# ir_ring_2022_neu_03.net
KiCad netlist of a schematic drawn in EAGLE
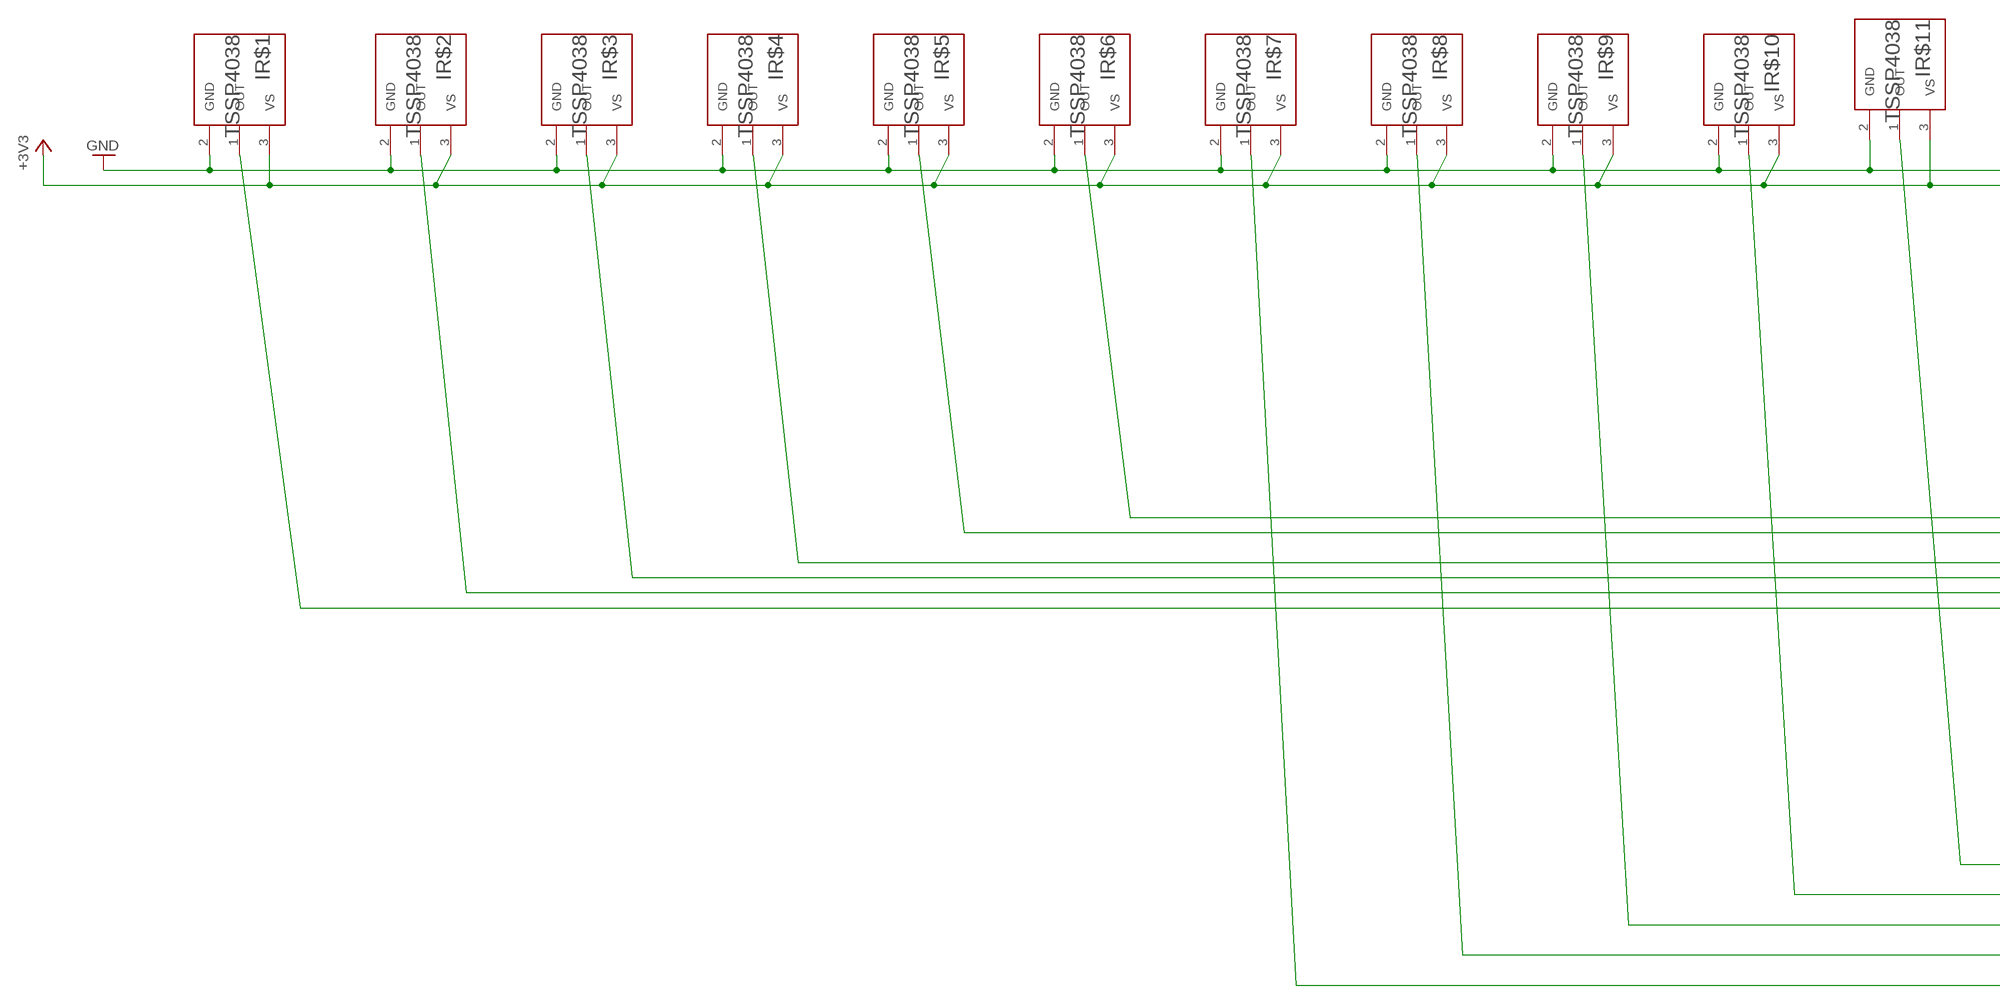
[diagram p0: schematic, sheet 1, part 1 of 2]
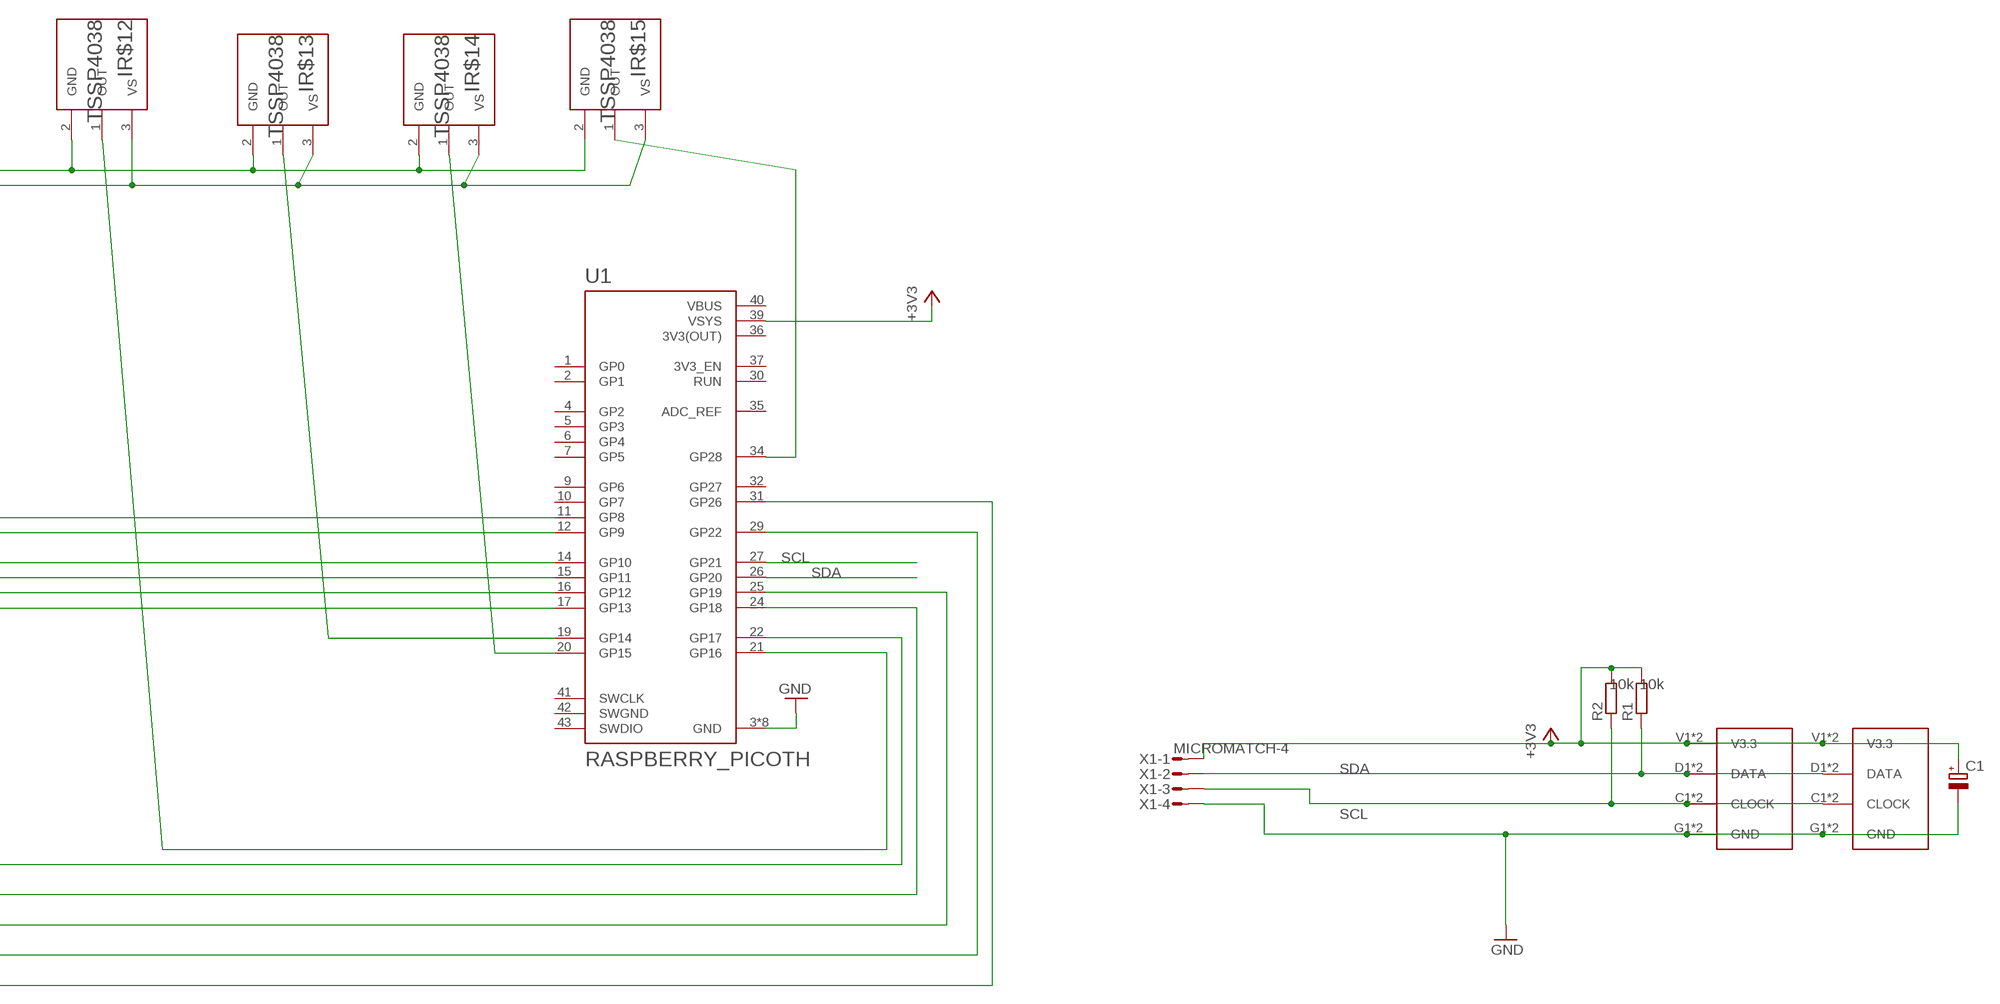
[diagram p1: schematic, sheet 1, part 2 of 2]

(export (version "E")
  (design (tool "Eeschema 10.0.6"))
  (components
    (comp (ref "C1")
      (value "CPOL-EUE2-5")
      (footprint "eagle-import:E2-5")
      (libsource (lib "eagle-import") (part "CPOL-EUE2-5"))
    )
    (comp (ref "IR$1")
      (value "TSSP4038")
      (footprint "eagle-import:XDCR_TSSP4038")
      (fields (field (name "MF") "Vishay Semiconductor"))
      (libsource (lib "eagle-import") (part "TSSP4038"))
    )
    (comp (ref "IR$2")
      (value "TSSP4038")
      (footprint "eagle-import:XDCR_TSSP4038")
      (fields (field (name "MF") "Vishay Semiconductor"))
      (libsource (lib "eagle-import") (part "TSSP4038"))
    )
    (comp (ref "IR$3")
      (value "TSSP4038")
      (footprint "eagle-import:XDCR_TSSP4038")
      (fields (field (name "MF") "Vishay Semiconductor"))
      (libsource (lib "eagle-import") (part "TSSP4038"))
    )
    (comp (ref "IR$4")
      (value "TSSP4038")
      (footprint "eagle-import:XDCR_TSSP4038")
      (fields (field (name "MF") "Vishay Semiconductor"))
      (libsource (lib "eagle-import") (part "TSSP4038"))
    )
    (comp (ref "IR$5")
      (value "TSSP4038")
      (footprint "eagle-import:XDCR_TSSP4038")
      (fields (field (name "MF") "Vishay Semiconductor"))
      (libsource (lib "eagle-import") (part "TSSP4038"))
    )
    (comp (ref "IR$6")
      (value "TSSP4038")
      (footprint "eagle-import:XDCR_TSSP4038")
      (fields (field (name "MF") "Vishay Semiconductor"))
      (libsource (lib "eagle-import") (part "TSSP4038"))
    )
    (comp (ref "IR$7")
      (value "TSSP4038")
      (footprint "eagle-import:XDCR_TSSP4038")
      (fields (field (name "MF") "Vishay Semiconductor"))
      (libsource (lib "eagle-import") (part "TSSP4038"))
    )
    (comp (ref "IR$8")
      (value "TSSP4038")
      (footprint "eagle-import:XDCR_TSSP4038")
      (fields (field (name "MF") "Vishay Semiconductor"))
      (libsource (lib "eagle-import") (part "TSSP4038"))
    )
    (comp (ref "IR$9")
      (value "TSSP4038")
      (footprint "eagle-import:XDCR_TSSP4038")
      (fields (field (name "MF") "Vishay Semiconductor"))
      (libsource (lib "eagle-import") (part "TSSP4038"))
    )
    (comp (ref "IR$10")
      (value "TSSP4038")
      (footprint "eagle-import:XDCR_TSSP4038")
      (fields (field (name "MF") "Vishay Semiconductor"))
      (libsource (lib "eagle-import") (part "TSSP4038"))
    )
    (comp (ref "IR$11")
      (value "TSSP4038")
      (footprint "eagle-import:XDCR_TSSP4038")
      (fields (field (name "MF") "Vishay Semiconductor"))
      (libsource (lib "eagle-import") (part "TSSP4038"))
    )
    (comp (ref "IR$12")
      (value "TSSP4038")
      (footprint "eagle-import:XDCR_TSSP4038")
      (fields (field (name "MF") "Vishay Semiconductor"))
      (libsource (lib "eagle-import") (part "TSSP4038"))
    )
    (comp (ref "IR$13")
      (value "TSSP4038")
      (footprint "eagle-import:XDCR_TSSP4038")
      (fields (field (name "MF") "Vishay Semiconductor"))
      (libsource (lib "eagle-import") (part "TSSP4038"))
    )
    (comp (ref "IR$14")
      (value "TSSP4038")
      (footprint "eagle-import:XDCR_TSSP4038")
      (fields (field (name "MF") "Vishay Semiconductor"))
      (libsource (lib "eagle-import") (part "TSSP4038"))
    )
    (comp (ref "IR$15")
      (value "TSSP4038")
      (footprint "eagle-import:XDCR_TSSP4038")
      (fields (field (name "MF") "Vishay Semiconductor"))
      (libsource (lib "eagle-import") (part "TSSP4038"))
    )
    (comp (ref "R1")
      (value "10k")
      (footprint "eagle-import:0204_7")
      (libsource (lib "eagle-import") (part "R-EU_0204/7"))
    )
    (comp (ref "R2")
      (value "10k")
      (footprint "eagle-import:0204_7")
      (libsource (lib "eagle-import") (part "R-EU_0204/7"))
    )
    (comp (ref "U$1")
      (value "TASTER_LED")
      (footprint "eagle-import:TASTER_LED")
      (libsource (lib "eagle-import") (part "TASTER_LED"))
    )
    (comp (ref "U$2")
      (value "TASTER_LED")
      (footprint "eagle-import:TASTER_LED")
      (libsource (lib "eagle-import") (part "TASTER_LED"))
    )
    (comp (ref "U1")
      (value "RASPBERRY_PICOTH")
      (footprint "eagle-import:PICO-PKG-TH")
      (libsource (lib "eagle-import") (part "RASPBERRY_PICOTH"))
    )
    (comp (ref "X1")
      (value "MICROMATCH-4")
      (footprint "eagle-import:MICROMATCH-4")
      (fields (field (name "MPN") "7-215464-4"))
      (libsource (lib "eagle-import") (part "MICROMATCH-4"))
    )
  )
  (nets
    (net (code "1") (name "+3V3") (class "Default")
      (node (ref "C1") (pin "+") (pinfunction "+_+") (pintype "passive"))
      (node (ref "IR$1") (pin "3") (pinfunction "VS_3") (pintype "power_in"))
      (node (ref "IR$10") (pin "3") (pinfunction "VS_3") (pintype "power_in"))
      (node (ref "IR$11") (pin "3") (pinfunction "VS_3") (pintype "power_in"))
      (node (ref "IR$12") (pin "3") (pinfunction "VS_3") (pintype "power_in"))
      (node (ref "IR$13") (pin "3") (pinfunction "VS_3") (pintype "power_in"))
      (node (ref "IR$14") (pin "3") (pinfunction "VS_3") (pintype "power_in"))
      (node (ref "IR$15") (pin "3") (pinfunction "VS_3") (pintype "power_in"))
      (node (ref "IR$2") (pin "3") (pinfunction "VS_3") (pintype "power_in"))
      (node (ref "IR$3") (pin "3") (pinfunction "VS_3") (pintype "power_in"))
      (node (ref "IR$4") (pin "3") (pinfunction "VS_3") (pintype "power_in"))
      (node (ref "IR$5") (pin "3") (pinfunction "VS_3") (pintype "power_in"))
      (node (ref "IR$6") (pin "3") (pinfunction "VS_3") (pintype "power_in"))
      (node (ref "IR$7") (pin "3") (pinfunction "VS_3") (pintype "power_in"))
      (node (ref "IR$8") (pin "3") (pinfunction "VS_3") (pintype "power_in"))
      (node (ref "IR$9") (pin "3") (pinfunction "VS_3") (pintype "power_in"))
      (node (ref "R1") (pin "2") (pinfunction "2_2") (pintype "passive"))
      (node (ref "R2") (pin "2") (pinfunction "2_2") (pintype "passive"))
      (node (ref "U$1") (pin "V1") (pinfunction "V3.3_V1") (pintype "bidirectional"))
      (node (ref "U$1") (pin "V2") (pinfunction "V3.3_V2") (pintype "bidirectional"))
      (node (ref "U$2") (pin "V1") (pinfunction "V3.3_V1") (pintype "bidirectional"))
      (node (ref "U$2") (pin "V2") (pinfunction "V3.3_V2") (pintype "bidirectional"))
      (node (ref "U1") (pin "39") (pinfunction "VSYS_39") (pintype "power_in"))
      (node (ref "X1") (pin "1") (pinfunction "S_1") (pintype "passive"))
    )
    (net (code "2") (name "/3V3(OUT)") (class "Default")
      (node (ref "U1") (pin "36") (pinfunction "3V3(OUT)_36") (pintype "power_in"))
    )
    (net (code "3") (name "/SCL") (class "Default")
      (node (ref "R2") (pin "1") (pinfunction "1_1") (pintype "passive"))
      (node (ref "U$1") (pin "C1") (pinfunction "CLOCK_C1") (pintype "bidirectional"))
      (node (ref "U$1") (pin "C2") (pinfunction "CLOCK_C2") (pintype "bidirectional"))
      (node (ref "U$2") (pin "C1") (pinfunction "CLOCK_C1") (pintype "bidirectional"))
      (node (ref "U$2") (pin "C2") (pinfunction "CLOCK_C2") (pintype "bidirectional"))
      (node (ref "U1") (pin "27") (pinfunction "GP21_27") (pintype "bidirectional"))
      (node (ref "X1") (pin "3") (pinfunction "S_3") (pintype "passive"))
    )
    (net (code "4") (name "/SDA") (class "Default")
      (node (ref "R1") (pin "1") (pinfunction "1_1") (pintype "passive"))
      (node (ref "U$1") (pin "D1") (pinfunction "DATA_D1") (pintype "bidirectional"))
      (node (ref "U$1") (pin "D2") (pinfunction "DATA_D2") (pintype "bidirectional"))
      (node (ref "U$2") (pin "D1") (pinfunction "DATA_D1") (pintype "bidirectional"))
      (node (ref "U$2") (pin "D2") (pinfunction "DATA_D2") (pintype "bidirectional"))
      (node (ref "U1") (pin "26") (pinfunction "GP20_26") (pintype "bidirectional"))
      (node (ref "X1") (pin "2") (pinfunction "S_2") (pintype "passive"))
    )
    (net (code "5") (name "/SWGND") (class "Default")
      (node (ref "U1") (pin "42") (pinfunction "SWGND_42") (pintype "power_in"))
    )
    (net (code "6") (name "/VBUS") (class "Default")
      (node (ref "U1") (pin "40") (pinfunction "VBUS_40") (pintype "power_in"))
    )
    (net (code "7") (name "GND") (class "Default")
      (node (ref "C1") (pin "-") (pinfunction "-_-") (pintype "passive"))
      (node (ref "IR$1") (pin "2") (pinfunction "GND_2") (pintype "power_in"))
      (node (ref "IR$10") (pin "2") (pinfunction "GND_2") (pintype "power_in"))
      (node (ref "IR$11") (pin "2") (pinfunction "GND_2") (pintype "power_in"))
      (node (ref "IR$12") (pin "2") (pinfunction "GND_2") (pintype "power_in"))
      (node (ref "IR$13") (pin "2") (pinfunction "GND_2") (pintype "power_in"))
      (node (ref "IR$14") (pin "2") (pinfunction "GND_2") (pintype "power_in"))
      (node (ref "IR$15") (pin "2") (pinfunction "GND_2") (pintype "power_in"))
      (node (ref "IR$2") (pin "2") (pinfunction "GND_2") (pintype "power_in"))
      (node (ref "IR$3") (pin "2") (pinfunction "GND_2") (pintype "power_in"))
      (node (ref "IR$4") (pin "2") (pinfunction "GND_2") (pintype "power_in"))
      (node (ref "IR$5") (pin "2") (pinfunction "GND_2") (pintype "power_in"))
      (node (ref "IR$6") (pin "2") (pinfunction "GND_2") (pintype "power_in"))
      (node (ref "IR$7") (pin "2") (pinfunction "GND_2") (pintype "power_in"))
      (node (ref "IR$8") (pin "2") (pinfunction "GND_2") (pintype "power_in"))
      (node (ref "IR$9") (pin "2") (pinfunction "GND_2") (pintype "power_in"))
      (node (ref "U$1") (pin "G1") (pinfunction "GND_G1") (pintype "bidirectional"))
      (node (ref "U$1") (pin "G2") (pinfunction "GND_G2") (pintype "bidirectional"))
      (node (ref "U$2") (pin "G1") (pinfunction "GND_G1") (pintype "bidirectional"))
      (node (ref "U$2") (pin "G2") (pinfunction "GND_G2") (pintype "bidirectional"))
      (node (ref "U1") (pin "13") (pinfunction "GND_13") (pintype "power_in"))
      (node (ref "U1") (pin "18") (pinfunction "GND_18") (pintype "power_in"))
      (node (ref "U1") (pin "23") (pinfunction "GND_23") (pintype "power_in"))
      (node (ref "U1") (pin "28") (pinfunction "GND_28") (pintype "power_in"))
      (node (ref "U1") (pin "3") (pinfunction "GND_3") (pintype "power_in"))
      (node (ref "U1") (pin "33") (pinfunction "GND_33") (pintype "power_in"))
      (node (ref "U1") (pin "38") (pinfunction "GND_38") (pintype "power_in"))
      (node (ref "U1") (pin "8") (pinfunction "GND_8") (pintype "power_in"))
      (node (ref "X1") (pin "4") (pinfunction "S_4") (pintype "passive"))
    )
    (net (code "8") (name "Net-(IR$1-OUT)") (class "Default")
      (node (ref "IR$1") (pin "1") (pinfunction "OUT_1") (pintype "output"))
      (node (ref "U1") (pin "17") (pinfunction "GP13_17") (pintype "bidirectional"))
    )
    (net (code "9") (name "Net-(IR$2-OUT)") (class "Default")
      (node (ref "IR$2") (pin "1") (pinfunction "OUT_1") (pintype "output"))
      (node (ref "U1") (pin "16") (pinfunction "GP12_16") (pintype "bidirectional"))
    )
    (net (code "10") (name "Net-(IR$3-OUT)") (class "Default")
      (node (ref "IR$3") (pin "1") (pinfunction "OUT_1") (pintype "output"))
      (node (ref "U1") (pin "15") (pinfunction "GP11_15") (pintype "bidirectional"))
    )
    (net (code "11") (name "Net-(IR$4-OUT)") (class "Default")
      (node (ref "IR$4") (pin "1") (pinfunction "OUT_1") (pintype "output"))
      (node (ref "U1") (pin "14") (pinfunction "GP10_14") (pintype "bidirectional"))
    )
    (net (code "12") (name "Net-(IR$5-OUT)") (class "Default")
      (node (ref "IR$5") (pin "1") (pinfunction "OUT_1") (pintype "output"))
      (node (ref "U1") (pin "12") (pinfunction "GP9_12") (pintype "bidirectional"))
    )
    (net (code "13") (name "Net-(IR$6-OUT)") (class "Default")
      (node (ref "IR$6") (pin "1") (pinfunction "OUT_1") (pintype "output"))
      (node (ref "U1") (pin "11") (pinfunction "GP8_11") (pintype "bidirectional"))
    )
    (net (code "14") (name "Net-(IR$7-OUT)") (class "Default")
      (node (ref "IR$7") (pin "1") (pinfunction "OUT_1") (pintype "output"))
      (node (ref "U1") (pin "31") (pinfunction "GP26_31") (pintype "bidirectional"))
    )
    (net (code "15") (name "Net-(IR$8-OUT)") (class "Default")
      (node (ref "IR$8") (pin "1") (pinfunction "OUT_1") (pintype "output"))
      (node (ref "U1") (pin "29") (pinfunction "GP22_29") (pintype "bidirectional"))
    )
    (net (code "16") (name "Net-(IR$9-OUT)") (class "Default")
      (node (ref "IR$9") (pin "1") (pinfunction "OUT_1") (pintype "output"))
      (node (ref "U1") (pin "25") (pinfunction "GP19_25") (pintype "bidirectional"))
    )
    (net (code "17") (name "Net-(IR$10-OUT)") (class "Default")
      (node (ref "IR$10") (pin "1") (pinfunction "OUT_1") (pintype "output"))
      (node (ref "U1") (pin "24") (pinfunction "GP18_24") (pintype "bidirectional"))
    )
    (net (code "18") (name "Net-(IR$11-OUT)") (class "Default")
      (node (ref "IR$11") (pin "1") (pinfunction "OUT_1") (pintype "output"))
      (node (ref "U1") (pin "22") (pinfunction "GP17_22") (pintype "bidirectional"))
    )
    (net (code "19") (name "Net-(IR$12-OUT)") (class "Default")
      (node (ref "IR$12") (pin "1") (pinfunction "OUT_1") (pintype "output"))
      (node (ref "U1") (pin "21") (pinfunction "GP16_21") (pintype "bidirectional"))
    )
    (net (code "20") (name "Net-(IR$13-OUT)") (class "Default")
      (node (ref "IR$13") (pin "1") (pinfunction "OUT_1") (pintype "output"))
      (node (ref "U1") (pin "19") (pinfunction "GP14_19") (pintype "bidirectional"))
    )
    (net (code "21") (name "Net-(IR$14-OUT)") (class "Default")
      (node (ref "IR$14") (pin "1") (pinfunction "OUT_1") (pintype "output"))
      (node (ref "U1") (pin "20") (pinfunction "GP15_20") (pintype "bidirectional"))
    )
    (net (code "22") (name "Net-(IR$15-OUT)") (class "Default")
      (node (ref "IR$15") (pin "1") (pinfunction "OUT_1") (pintype "output"))
      (node (ref "U1") (pin "34") (pinfunction "GP28_34") (pintype "bidirectional"))
    )
    (net (code "23") (name "unconnected-(U1-3V3_EN-Pad37)") (class "Default")
      (node (ref "U1") (pin "37") (pinfunction "3V3_EN_37") (pintype "input"))
    )
    (net (code "24") (name "unconnected-(U1-ADC_REF-Pad35)") (class "Default")
      (node (ref "U1") (pin "35") (pinfunction "ADC_REF_35") (pintype "input"))
    )
    (net (code "25") (name "unconnected-(U1-GP0-Pad1)") (class "Default")
      (node (ref "U1") (pin "1") (pinfunction "GP0_1") (pintype "bidirectional"))
    )
    (net (code "26") (name "unconnected-(U1-GP1-Pad2)") (class "Default")
      (node (ref "U1") (pin "2") (pinfunction "GP1_2") (pintype "bidirectional"))
    )
    (net (code "27") (name "unconnected-(U1-GP2-Pad4)") (class "Default")
      (node (ref "U1") (pin "4") (pinfunction "GP2_4") (pintype "bidirectional"))
    )
    (net (code "28") (name "unconnected-(U1-GP3-Pad5)") (class "Default")
      (node (ref "U1") (pin "5") (pinfunction "GP3_5") (pintype "bidirectional"))
    )
    (net (code "29") (name "unconnected-(U1-GP4-Pad6)") (class "Default")
      (node (ref "U1") (pin "6") (pinfunction "GP4_6") (pintype "bidirectional"))
    )
    (net (code "30") (name "unconnected-(U1-GP5-Pad7)") (class "Default")
      (node (ref "U1") (pin "7") (pinfunction "GP5_7") (pintype "bidirectional"))
    )
    (net (code "31") (name "unconnected-(U1-GP6-Pad9)") (class "Default")
      (node (ref "U1") (pin "9") (pinfunction "GP6_9") (pintype "bidirectional"))
    )
    (net (code "32") (name "unconnected-(U1-GP7-Pad10)") (class "Default")
      (node (ref "U1") (pin "10") (pinfunction "GP7_10") (pintype "bidirectional"))
    )
    (net (code "33") (name "unconnected-(U1-GP27-Pad32)") (class "Default")
      (node (ref "U1") (pin "32") (pinfunction "GP27_32") (pintype "bidirectional"))
    )
    (net (code "34") (name "unconnected-(U1-RUN-Pad30)") (class "Default")
      (node (ref "U1") (pin "30") (pinfunction "RUN_30") (pintype "input"))
    )
    (net (code "35") (name "unconnected-(U1-SWCLK-Pad41)") (class "Default")
      (node (ref "U1") (pin "41") (pinfunction "SWCLK_41") (pintype "input"))
    )
    (net (code "36") (name "unconnected-(U1-SWDIO-Pad43)") (class "Default")
      (node (ref "U1") (pin "43") (pinfunction "SWDIO_43") (pintype "bidirectional"))
    )
  )
)
